# Rolladen5.net
KiCad netlist of a schematic drawn in EAGLE
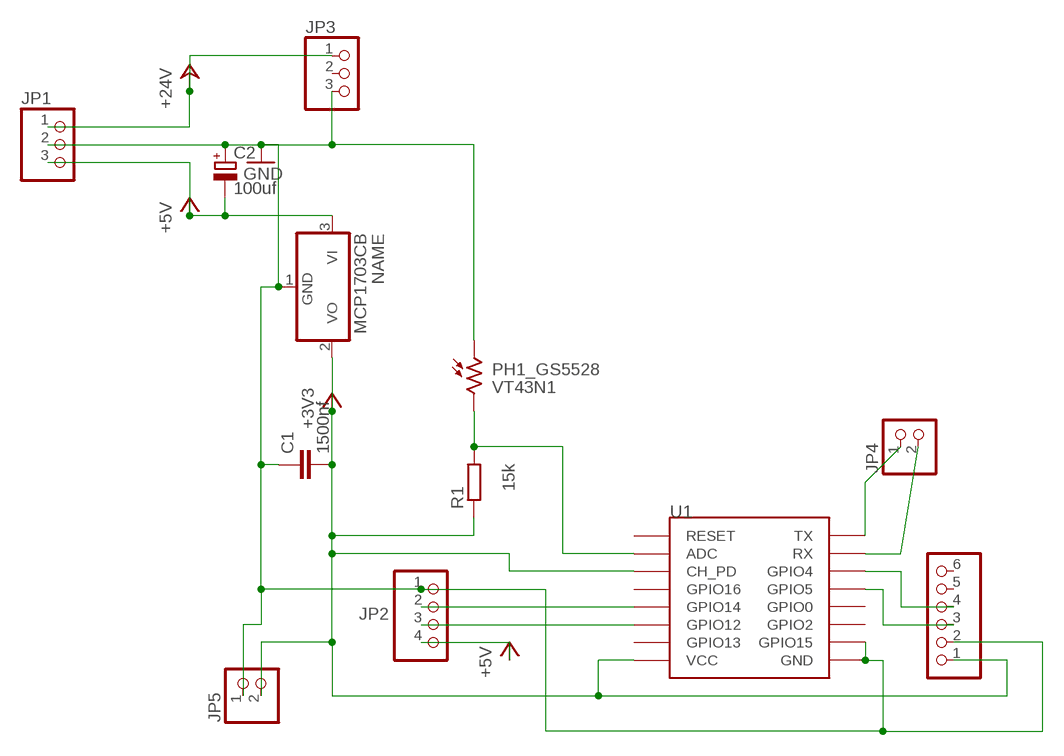
[diagram p0: schematic, sheet 1]

(export (version "E")
  (design (tool "Eeschema 10.0.6"))
  (components
    (comp (ref "C1")
      (value "1500nf")
      (footprint "eagle-import:C025-024X044")
      (libsource (lib "eagle-import") (part "C-EU025-024X044"))
    )
    (comp (ref "C2")
      (value "100uf")
      (footprint "eagle-import:E2,5-6")
      (libsource (lib "eagle-import") (part "CPOL-EUE2.5-6"))
    )
    (comp (ref "IC1_MCP1700")
      (value "MCP1703CB")
      (footprint "eagle-import:SOT23")
      (libsource (lib "eagle-import") (part "MCP1703CB"))
    )
    (comp (ref "JP1")
      (value "PINHD-1X3/90")
      (footprint "eagle-import:1X03_90")
      (libsource (lib "eagle-import") (part "PINHD-1X3/90"))
    )
    (comp (ref "JP2")
      (value "PINHD-1X4")
      (footprint "eagle-import:1X04")
      (libsource (lib "eagle-import") (part "PINHD-1X4"))
    )
    (comp (ref "JP3")
      (value "PINHD-1X3")
      (footprint "eagle-import:1X03")
      (libsource (lib "eagle-import") (part "PINHD-1X3"))
    )
    (comp (ref "JP3TMP102")
      (value "PINHD-1X6")
      (footprint "eagle-import:1X06")
      (libsource (lib "eagle-import") (part "PINHD-1X6"))
    )
    (comp (ref "JP4")
      (value "PINHD-1X2")
      (footprint "eagle-import:1X02")
      (libsource (lib "eagle-import") (part "PINHD-1X2"))
    )
    (comp (ref "JP5")
      (value "PINHD-1X2")
      (footprint "eagle-import:1X02")
      (libsource (lib "eagle-import") (part "PINHD-1X2"))
    )
    (comp (ref "PH1_GS5528")
      (value "VT43N1")
      (footprint "eagle-import:VT400")
      (libsource (lib "eagle-import") (part "VT43N1"))
    )
    (comp (ref "R1")
      (value "15k")
      (footprint "eagle-import:0207_10")
      (libsource (lib "eagle-import") (part "R-EU_0207/10"))
    )
    (comp (ref "U1")
      (value "ESP12")
      (footprint "eagle-import:ESP12")
      (libsource (lib "eagle-import") (part "ESP12"))
    )
  )
  (nets
    (net (code "1") (name "+3V3") (class "Default")
      (node (ref "C1") (pin "2") (pinfunction "2_2") (pintype "passive"))
      (node (ref "IC1_MCP1700") (pin "2") (pinfunction "VO_2") (pintype "passive"))
      (node (ref "JP3TMP102") (pin "1") (pinfunction "1_1") (pintype "passive"))
      (node (ref "JP5") (pin "2") (pinfunction "2_2") (pintype "passive"))
      (node (ref "R1") (pin "1") (pinfunction "1_1") (pintype "passive"))
      (node (ref "U1") (pin "CH_PD") (pinfunction "CH_PD_CH_PD") (pintype "bidirectional"))
      (node (ref "U1") (pin "VCC") (pinfunction "VCC_VCC") (pintype "bidirectional"))
    )
    (net (code "2") (name "+5V") (class "Default")
      (node (ref "C2") (pin "-") (pinfunction "-_-") (pintype "passive"))
      (node (ref "IC1_MCP1700") (pin "3") (pinfunction "VI_3") (pintype "input"))
      (node (ref "JP1") (pin "3") (pinfunction "3_3") (pintype "passive"))
      (node (ref "JP2") (pin "4") (pinfunction "4_4") (pintype "passive"))
    )
    (net (code "3") (name "+24V") (class "Default")
      (node (ref "JP1") (pin "1") (pinfunction "1_1") (pintype "passive"))
      (node (ref "JP3") (pin "1") (pinfunction "1_1") (pintype "passive"))
    )
    (net (code "4") (name "GND") (class "Default")
      (node (ref "C1") (pin "1") (pinfunction "1_1") (pintype "passive"))
      (node (ref "C2") (pin "+") (pinfunction "+_+") (pintype "passive"))
      (node (ref "IC1_MCP1700") (pin "1") (pinfunction "GND_1") (pintype "passive"))
      (node (ref "JP1") (pin "2") (pinfunction "2_2") (pintype "passive"))
      (node (ref "JP2") (pin "1") (pinfunction "1_1") (pintype "passive"))
      (node (ref "JP3") (pin "3") (pinfunction "3_3") (pintype "passive"))
      (node (ref "JP3TMP102") (pin "2") (pinfunction "2_2") (pintype "passive"))
      (node (ref "JP5") (pin "1") (pinfunction "1_1") (pintype "passive"))
      (node (ref "PH1_GS5528") (pin "1") (pinfunction "1_1") (pintype "passive"))
      (node (ref "U1") (pin "GND") (pinfunction "GND_GND") (pintype "bidirectional"))
      (node (ref "U1") (pin "GPIO15") (pinfunction "GPIO15_GPIO15") (pintype "bidirectional"))
    )
    (net (code "5") (name "Net-(JP2-Pad2)") (class "Default")
      (node (ref "JP2") (pin "2") (pinfunction "2_2") (pintype "passive"))
      (node (ref "U1") (pin "GPIO14") (pinfunction "GPIO14_GPIO14") (pintype "bidirectional"))
    )
    (net (code "6") (name "Net-(JP2-Pad3)") (class "Default")
      (node (ref "JP2") (pin "3") (pinfunction "3_3") (pintype "passive"))
      (node (ref "U1") (pin "GPIO12") (pinfunction "GPIO12_GPIO12") (pintype "bidirectional"))
    )
    (net (code "7") (name "Net-(JP3TMP102-Pad3)") (class "Default")
      (node (ref "JP3TMP102") (pin "3") (pinfunction "3_3") (pintype "passive"))
      (node (ref "U1") (pin "GPIO5") (pinfunction "GPIO5_GPIO5") (pintype "bidirectional"))
    )
    (net (code "8") (name "Net-(JP3TMP102-Pad4)") (class "Default")
      (node (ref "JP3TMP102") (pin "4") (pinfunction "4_4") (pintype "passive"))
      (node (ref "U1") (pin "GPIO4") (pinfunction "GPIO4_GPIO4") (pintype "bidirectional"))
    )
    (net (code "9") (name "Net-(JP4-Pad1)") (class "Default")
      (node (ref "JP4") (pin "1") (pinfunction "1_1") (pintype "passive"))
      (node (ref "U1") (pin "TX") (pinfunction "TX_TX") (pintype "bidirectional"))
    )
    (net (code "10") (name "Net-(JP4-Pad2)") (class "Default")
      (node (ref "JP4") (pin "2") (pinfunction "2_2") (pintype "passive"))
      (node (ref "U1") (pin "RX") (pinfunction "RX_RX") (pintype "bidirectional"))
    )
    (net (code "11") (name "Net-(PH1_GS5528-Pad2)") (class "Default")
      (node (ref "PH1_GS5528") (pin "2") (pinfunction "2_2") (pintype "passive"))
      (node (ref "R1") (pin "2") (pinfunction "2_2") (pintype "passive"))
      (node (ref "U1") (pin "ADC") (pinfunction "ADC_ADC") (pintype "bidirectional"))
    )
    (net (code "12") (name "unconnected-(JP3-Pad2)") (class "Default")
      (node (ref "JP3") (pin "2") (pinfunction "2_2") (pintype "passive"))
    )
    (net (code "13") (name "unconnected-(JP3TMP102-Pad5)") (class "Default")
      (node (ref "JP3TMP102") (pin "5") (pinfunction "5_5") (pintype "passive"))
    )
    (net (code "14") (name "unconnected-(JP3TMP102-Pad6)") (class "Default")
      (node (ref "JP3TMP102") (pin "6") (pinfunction "6_6") (pintype "passive"))
    )
    (net (code "15") (name "unconnected-(U1-PadGPIO0)") (class "Default")
      (node (ref "U1") (pin "GPIO0") (pinfunction "GPIO0_GPIO0") (pintype "bidirectional"))
    )
    (net (code "16") (name "unconnected-(U1-PadGPIO2)") (class "Default")
      (node (ref "U1") (pin "GPIO2") (pinfunction "GPIO2_GPIO2") (pintype "bidirectional"))
    )
    (net (code "17") (name "unconnected-(U1-PadGPIO13)") (class "Default")
      (node (ref "U1") (pin "GPIO13") (pinfunction "GPIO13_GPIO13") (pintype "bidirectional"))
    )
    (net (code "18") (name "unconnected-(U1-PadGPIO16)") (class "Default")
      (node (ref "U1") (pin "GPIO16") (pinfunction "GPIO16_GPIO16") (pintype "bidirectional"))
    )
    (net (code "19") (name "unconnected-(U1-PadRESET)") (class "Default")
      (node (ref "U1") (pin "RESET") (pinfunction "RESET_RESET") (pintype "bidirectional"))
    )
  )
)
